# EmitterConnector.net
KiCad netlist of a schematic drawn in Altium Designer
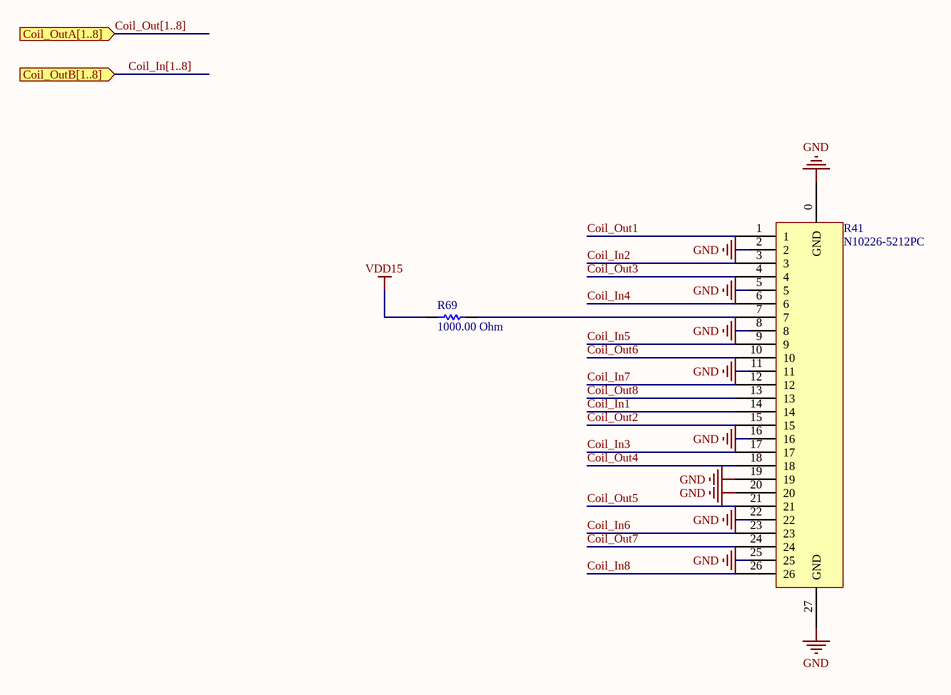
[diagram p0: EmitterConnector.SchDoc]

(export (version "E")
  (design (tool "Eeschema 10.0.6"))
  (components
    (comp (ref "R41")
      (value "N10226-5212PC")
      (footprint "CONN MINI-D 26POS R/A RECPT")
      (description "CONN MINI-D 26POS R/A RECPT")
      (fields (field (name "MANUFACTURER") "3M") (field (name "PUBLISHER") "Altium Limited"))
      (libsource (lib "AnserEMT") (part "N10226-5212PC"))
    )
    (comp (ref "R69")
      (value "1000.00 Ohm")
      (footprint "RESC0603(1608)_L")
      (description "1K 0.1W 5% 0603 (1608 Metric)  SMD")
      (fields (field (name "TOLERANCE") "5 %") (field (name "POWER") "0.1 W"))
      (libsource (lib "Altium Content Vault") (part "CMP-1012-00074-1"))
    )
  )
  (nets
    (net (code "1") (name "/Coil_In1") (class "Default")
      (node (ref "R41") (pin "14") (pinfunction "14_14") (pintype "passive"))
    )
    (net (code "2") (name "/Coil_In2") (class "Default")
      (node (ref "R41") (pin "3") (pinfunction "3_3") (pintype "passive"))
    )
    (net (code "3") (name "/Coil_In3") (class "Default")
      (node (ref "R41") (pin "17") (pinfunction "17_17") (pintype "passive"))
    )
    (net (code "4") (name "/Coil_In4") (class "Default")
      (node (ref "R41") (pin "6") (pinfunction "6_6") (pintype "passive"))
    )
    (net (code "5") (name "/Coil_In5") (class "Default")
      (node (ref "R41") (pin "9") (pinfunction "9_9") (pintype "passive"))
    )
    (net (code "6") (name "/Coil_In6") (class "Default")
      (node (ref "R41") (pin "23") (pinfunction "23_23") (pintype "passive"))
    )
    (net (code "7") (name "/Coil_In7") (class "Default")
      (node (ref "R41") (pin "12") (pinfunction "12_12") (pintype "passive"))
    )
    (net (code "8") (name "/Coil_In8") (class "Default")
      (node (ref "R41") (pin "26") (pinfunction "26_26") (pintype "passive"))
    )
    (net (code "10") (name "/Coil_Out1") (class "Default")
      (node (ref "R41") (pin "1") (pinfunction "1_1") (pintype "passive"))
    )
    (net (code "11") (name "/Coil_Out2") (class "Default")
      (node (ref "R41") (pin "15") (pinfunction "15_15") (pintype "passive"))
    )
    (net (code "12") (name "/Coil_Out3") (class "Default")
      (node (ref "R41") (pin "4") (pinfunction "4_4") (pintype "passive"))
    )
    (net (code "13") (name "/Coil_Out4") (class "Default")
      (node (ref "R41") (pin "18") (pinfunction "18_18") (pintype "passive"))
    )
    (net (code "14") (name "/Coil_Out5") (class "Default")
      (node (ref "R41") (pin "21") (pinfunction "21_21") (pintype "passive"))
    )
    (net (code "15") (name "/Coil_Out6") (class "Default")
      (node (ref "R41") (pin "10") (pinfunction "10_10") (pintype "passive"))
    )
    (net (code "16") (name "/Coil_Out7") (class "Default")
      (node (ref "R41") (pin "24") (pinfunction "24_24") (pintype "passive"))
    )
    (net (code "17") (name "/Coil_Out8") (class "Default")
      (node (ref "R41") (pin "13") (pinfunction "13_13") (pintype "passive"))
    )
    (net (code "19") (name "GND") (class "Default")
      (node (ref "R41") (pin "0") (pinfunction "GND_0") (pintype "passive"))
      (node (ref "R41") (pin "11") (pinfunction "11_11") (pintype "passive"))
      (node (ref "R41") (pin "16") (pinfunction "16_16") (pintype "passive"))
      (node (ref "R41") (pin "19") (pinfunction "19_19") (pintype "passive"))
      (node (ref "R41") (pin "2") (pinfunction "2_2") (pintype "passive"))
      (node (ref "R41") (pin "20") (pinfunction "20_20") (pintype "passive"))
      (node (ref "R41") (pin "22") (pinfunction "22_22") (pintype "passive"))
      (node (ref "R41") (pin "25") (pinfunction "25_25") (pintype "passive"))
      (node (ref "R41") (pin "27") (pinfunction "GND_27") (pintype "passive"))
      (node (ref "R41") (pin "5") (pinfunction "5_5") (pintype "passive"))
      (node (ref "R41") (pin "8") (pinfunction "8_8") (pintype "passive"))
    )
    (net (code "20") (name "Net-(R41-Pad7)") (class "Default")
      (node (ref "R41") (pin "7") (pinfunction "7_7") (pintype "passive"))
      (node (ref "R69") (pin "2") (pinfunction "2_2") (pintype "passive"))
    )
    (net (code "21") (name "VDD15") (class "Default")
      (node (ref "R69") (pin "1") (pinfunction "1_1") (pintype "passive"))
    )
  )
)
